# Banana2USB.net
KiCad netlist of a schematic drawn in Altium Designer
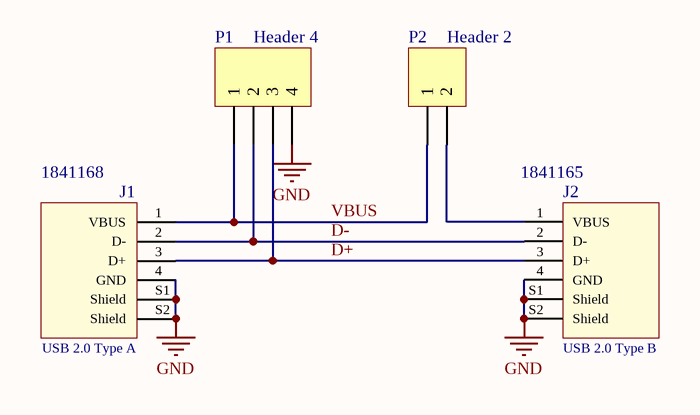
[diagram p0: Banana2USB.SchDoc]

(export (version "E")
  (design (tool "Eeschema 10.0.6"))
  (components
    (comp (ref "J1")
      (value "USB 2.0 Type A")
      (footprint "614004135023")
      (description "USB 2.0 Type A Vertical THT WR-COM")
      (fields
        (field (name "PART NUMBER") "614004135023")
        (field (name "SUPPLIER PART NUMBER 1") "1841168")
        (field (name "PUBLISHER") "Wurth Elektronik")
      )
      (libsource (lib "ALTIUM-WR-COM-rev18a") (part "614004135023"))
    )
    (comp (ref "J2")
      (value "USB 2.0 Type B")
      (footprint "61400413321")
      (description "USB 2.0 Type B Vertical THT WR-COM")
      (fields
        (field (name "PART NUMBER") "61400413321")
        (field (name "SUPPLIER PART NUMBER 1") "1841165")
        (field (name "PUBLISHER") "Wurth Elektronik")
      )
      (libsource (lib "ALTIUM-WR-COM-rev18a") (part "61400413321"))
    )
    (comp (ref "P1")
      (value "Header 4")
      (footprint "HDR1X4")
      (description "Header, 4-Pin")
      (fields (field (name "PUBLISHER") "Altium Limited"))
      (libsource (lib "Miscellaneous Connectors") (part "Header 4"))
    )
    (comp (ref "P2")
      (value "Header 2")
      (footprint "HDR1X2")
      (description "Header, 2-Pin")
      (fields (field (name "PUBLISHER") "Altium Limited"))
      (libsource (lib "Miscellaneous Connectors") (part "Header 2"))
    )
  )
  (nets
    (net (code "1") (name "/D+") (class "Default")
      (node (ref "J1") (pin "3") (pinfunction "D+_3") (pintype "passive"))
      (node (ref "J2") (pin "3") (pinfunction "D+_3") (pintype "passive"))
      (node (ref "P1") (pin "3") (pinfunction "3_3") (pintype "passive"))
    )
    (net (code "2") (name "/D-") (class "Default")
      (node (ref "J1") (pin "2") (pinfunction "D-_2") (pintype "passive"))
      (node (ref "J2") (pin "2") (pinfunction "D-_2") (pintype "passive"))
      (node (ref "P1") (pin "2") (pinfunction "2_2") (pintype "passive"))
    )
    (net (code "3") (name "/VBUS") (class "Default")
      (node (ref "J1") (pin "1") (pinfunction "VBUS_1") (pintype "passive"))
      (node (ref "P1") (pin "1") (pinfunction "1_1") (pintype "passive"))
      (node (ref "P2") (pin "1") (pinfunction "1_1") (pintype "passive"))
    )
    (net (code "4") (name "GND") (class "Default")
      (node (ref "J1") (pin "4") (pinfunction "GND_4") (pintype "passive"))
      (node (ref "J1") (pin "S1") (pinfunction "Shield_S1") (pintype "passive"))
      (node (ref "J1") (pin "S2") (pinfunction "Shield_S2") (pintype "passive"))
      (node (ref "J2") (pin "4") (pinfunction "GND_4") (pintype "passive"))
      (node (ref "J2") (pin "S1") (pinfunction "Shield_S1") (pintype "passive"))
      (node (ref "J2") (pin "S2") (pinfunction "Shield_S2") (pintype "passive"))
      (node (ref "P1") (pin "4") (pinfunction "4_4") (pintype "passive"))
    )
    (net (code "5") (name "Net-(J2-VBUS)") (class "Default")
      (node (ref "J2") (pin "1") (pinfunction "VBUS_1") (pintype "passive"))
      (node (ref "P2") (pin "2") (pinfunction "2_2") (pintype "passive"))
    )
  )
)
